# TunnelingAmp.net
KiCad netlist of a schematic drawn in EAGLE
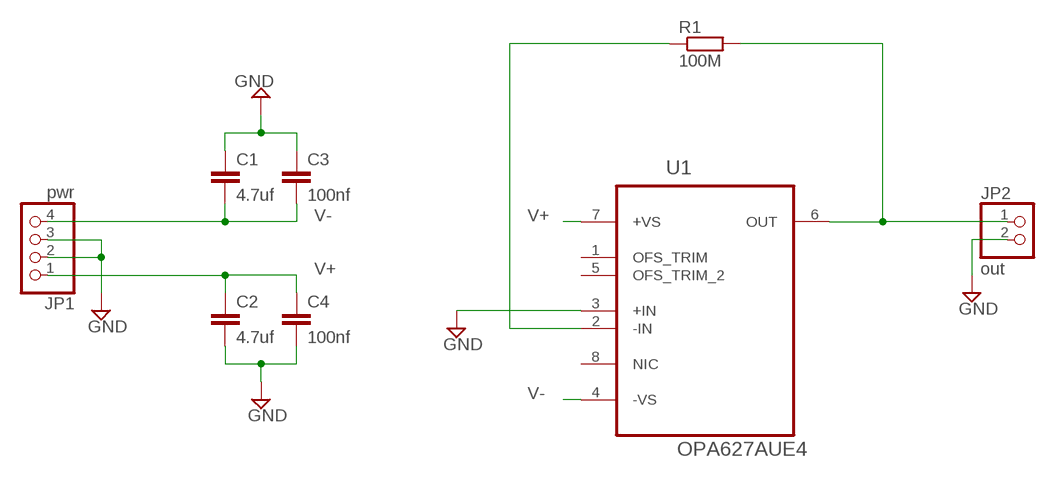
[diagram p0: schematic, sheet 1]

(export (version "E")
  (design (tool "Eeschema 10.0.6"))
  (components
    (comp (ref "C1")
      (value "4.7uf")
      (footprint "eagle-import:C1210")
      (libsource (lib "eagle-import") (part "C-EUC1210"))
    )
    (comp (ref "C2")
      (value "4.7uf")
      (footprint "eagle-import:C1210")
      (libsource (lib "eagle-import") (part "C-EUC1210"))
    )
    (comp (ref "C3")
      (value "100nf")
      (footprint "eagle-import:C0603")
      (libsource (lib "eagle-import") (part "C-EUC0603"))
    )
    (comp (ref "C4")
      (value "100nf")
      (footprint "eagle-import:C0603")
      (libsource (lib "eagle-import") (part "C-EUC0603"))
    )
    (comp (ref "JP1")
      (value "pwr")
      (footprint "eagle-import:1X04")
      (libsource (lib "eagle-import") (part "PINHD-1X4"))
    )
    (comp (ref "JP2")
      (value "out")
      (footprint "eagle-import:1X02")
      (libsource (lib "eagle-import") (part "PINHD-1X2"))
    )
    (comp (ref "R1")
      (value "100M")
      (footprint "eagle-import:R0805")
      (libsource (lib "eagle-import") (part "R-EU_R0805"))
    )
    (comp (ref "U1")
      (value "OPA627AUE4")
      (footprint "eagle-import:SOIC127P600X175-8N")
      (libsource (lib "eagle-import") (part "OPA627AUE4"))
    )
  )
  (nets
    (net (code "1") (name "/V+") (class "Default")
      (node (ref "C2") (pin "1") (pinfunction "1_1") (pintype "passive"))
      (node (ref "C4") (pin "1") (pinfunction "1_1") (pintype "passive"))
      (node (ref "JP1") (pin "1") (pinfunction "1_1") (pintype "passive"))
      (node (ref "U1") (pin "7") (pinfunction "+VS_7") (pintype "power_in"))
    )
    (net (code "2") (name "/V-") (class "Default")
      (node (ref "C1") (pin "2") (pinfunction "2_2") (pintype "passive"))
      (node (ref "C3") (pin "2") (pinfunction "2_2") (pintype "passive"))
      (node (ref "JP1") (pin "4") (pinfunction "4_4") (pintype "passive"))
      (node (ref "U1") (pin "4") (pinfunction "-VS_4") (pintype "power_in"))
    )
    (net (code "3") (name "GND") (class "Default")
      (node (ref "C1") (pin "1") (pinfunction "1_1") (pintype "passive"))
      (node (ref "C2") (pin "2") (pinfunction "2_2") (pintype "passive"))
      (node (ref "C3") (pin "1") (pinfunction "1_1") (pintype "passive"))
      (node (ref "C4") (pin "2") (pinfunction "2_2") (pintype "passive"))
      (node (ref "JP1") (pin "2") (pinfunction "2_2") (pintype "passive"))
      (node (ref "JP1") (pin "3") (pinfunction "3_3") (pintype "passive"))
      (node (ref "JP2") (pin "2") (pinfunction "2_2") (pintype "passive"))
      (node (ref "U1") (pin "3") (pinfunction "+IN_3") (pintype "input"))
    )
    (net (code "4") (name "Net-(U1--IN)") (class "Default")
      (node (ref "R1") (pin "1") (pinfunction "1_1") (pintype "passive"))
      (node (ref "U1") (pin "2") (pinfunction "-IN_2") (pintype "input"))
    )
    (net (code "5") (name "Net-(U1-OUT)") (class "Default")
      (node (ref "JP2") (pin "1") (pinfunction "1_1") (pintype "passive"))
      (node (ref "R1") (pin "2") (pinfunction "2_2") (pintype "passive"))
      (node (ref "U1") (pin "6") (pinfunction "OUT_6") (pintype "output"))
    )
    (net (code "6") (name "unconnected-(U1-NIC-Pad8)") (class "Default")
      (node (ref "U1") (pin "8") (pinfunction "NIC_8") (pintype "no_connect"))
    )
    (net (code "7") (name "unconnected-(U1-OFS_TRIM-Pad1)") (class "Default")
      (node (ref "U1") (pin "1") (pinfunction "OFS_TRIM_1") (pintype "passive"))
    )
    (net (code "8") (name "unconnected-(U1-OFS_TRIM_2-Pad5)") (class "Default")
      (node (ref "U1") (pin "5") (pinfunction "OFS_TRIM_2_5") (pintype "passive"))
    )
  )
)
